# Sheet1.net
KiCad netlist of a schematic drawn in Altium Designer
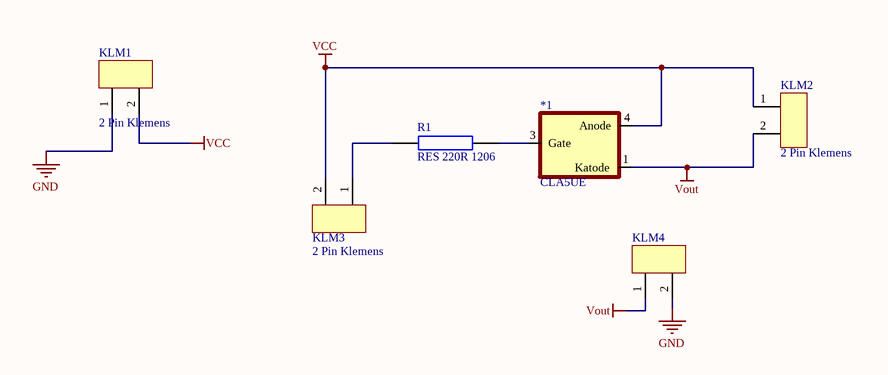
[diagram p0: Sheet1.SchDoc]

(export (version "E")
  (design (tool "Eeschema 10.0.6"))
  (components
    (comp (ref "*1")
      (value "CLA5UE")
      (footprint "DPAK229P990X239-4N")
      (libsource (lib "Schlib") (part "CLA5UE"))
    )
    (comp (ref "KLM1")
      (value "2 Pin Klemens")
      (footprint "5.08mm-2 pin")
      (description "5.08mm 2 pin klemens")
      (libsource (lib "Udemy_Schlib1") (part "2 Pin Klemens"))
    )
    (comp (ref "KLM2")
      (value "2 Pin Klemens")
      (footprint "5.08mm-2 pin")
      (description "5.08mm 2 pin klemens")
      (libsource (lib "") (part "2 Pin Klemens_1"))
    )
    (comp (ref "KLM3")
      (value "2 Pin Klemens")
      (footprint "5.08mm-2 pin")
      (description "5.08mm 2 pin klemens")
      (libsource (lib "") (part "2 Pin Klemens_2"))
    )
    (comp (ref "KLM4")
      (value "2 Pin Klemens")
      (footprint "5.08mm-2 pin")
      (description "5.08mm 2 pin klemens")
      (libsource (lib "Udemy_Schlib1") (part "2 Pin Klemens"))
    )
    (comp (ref "R1")
      (value "RES 220R 1206")
      (footprint "RES_1206")
      (libsource (lib "Udemy_Schlib1") (part "RES 220R 1206"))
    )
  )
  (nets
    (net (code "1") (name "GND") (class "Default")
      (node (ref "KLM1") (pin "1") (pintype "passive"))
      (node (ref "KLM4") (pin "2") (pintype "passive"))
    )
    (net (code "2") (name "Net-(*1-Gate)") (class "Default")
      (node (ref "*1") (pin "3") (pinfunction "Gate_3") (pintype "passive"))
      (node (ref "R1") (pin "2") (pintype "passive"))
    )
    (net (code "3") (name "Net-(KLM3-Pad1)") (class "Default")
      (node (ref "KLM3") (pin "1") (pintype "passive"))
      (node (ref "R1") (pin "1") (pintype "passive"))
    )
    (net (code "4") (name "VCC") (class "Default")
      (node (ref "*1") (pin "4") (pinfunction "Anode_4") (pintype "passive"))
      (node (ref "KLM1") (pin "2") (pintype "passive"))
      (node (ref "KLM2") (pin "1") (pintype "passive"))
      (node (ref "KLM3") (pin "2") (pintype "passive"))
    )
    (net (code "5") (name "Vout") (class "Default")
      (node (ref "*1") (pin "1") (pinfunction "Katode_1") (pintype "passive"))
      (node (ref "KLM2") (pin "2") (pintype "passive"))
      (node (ref "KLM4") (pin "1") (pintype "passive"))
    )
  )
)
